# 2.net
KiCad netlist of a schematic drawn in EAGLE
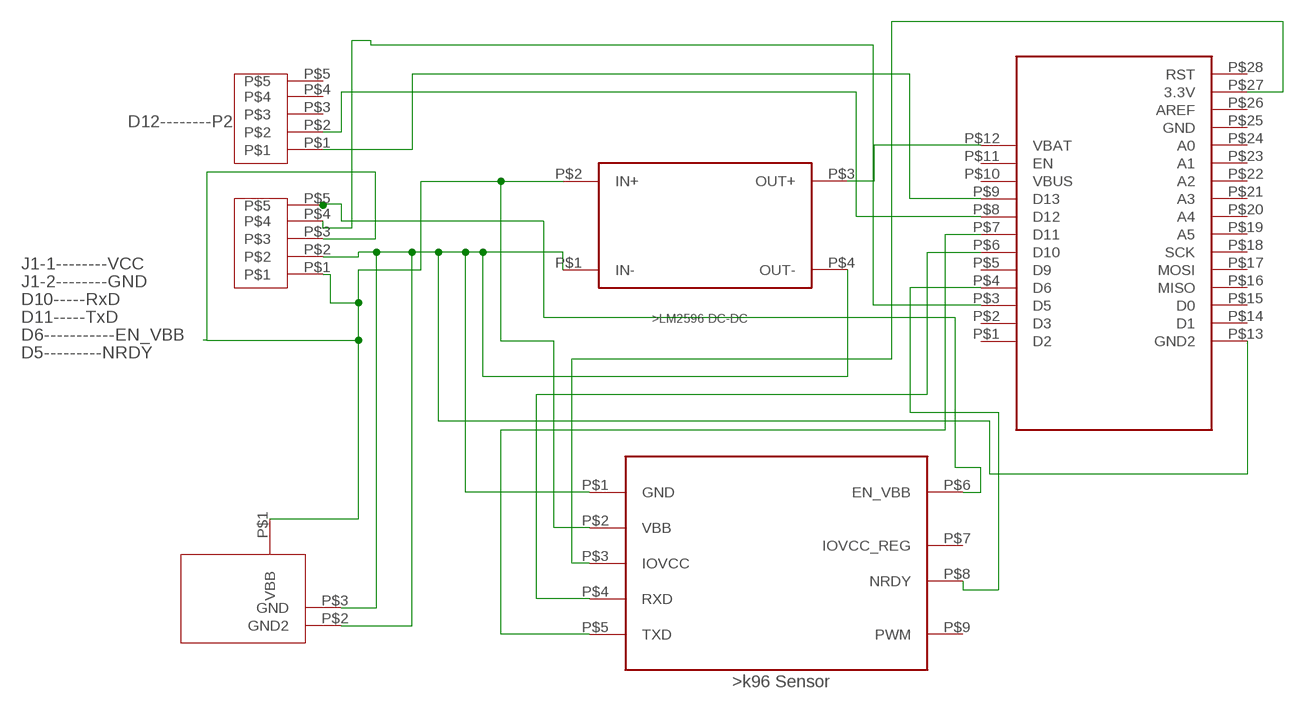
[diagram p0: schematic, sheet 1]

(export (version "E")
  (design (tool "Eeschema 10.0.6"))
  (components
    (comp (ref "DCDC1")
      (value "DCDC")
      (footprint "eagle-import:DCDC")
      (libsource (lib "eagle-import") (part "DCDC"))
    )
    (comp (ref "FEATHER1")
      (value "FEATHER")
      (footprint "eagle-import:FEATHER")
      (libsource (lib "eagle-import") (part "FEATHER"))
    )
    (comp (ref "K96SENSOR1")
      (value "K96SENSOR")
      (footprint "eagle-import:K96SENSOR")
      (libsource (lib "eagle-import") (part "K96SENSOR"))
    )
    (comp (ref "PIN1")
      (value "PIN")
      (footprint "eagle-import:PIN")
      (libsource (lib "eagle-import") (part "PIN"))
    )
    (comp (ref "PIN2")
      (value "PIN")
      (footprint "eagle-import:PIN")
      (libsource (lib "eagle-import") (part "PIN"))
    )
    (comp (ref "U$1")
      (value "POWER")
      (footprint "eagle-import:POWERIN")
      (libsource (lib "eagle-import") (part "POWER"))
    )
  )
  (nets
    (net (code "1") (name "Net-(DCDC1-IN+)") (class "Default")
      (node (ref "DCDC1") (pin "P$2") (pinfunction "IN+_P$2") (pintype "bidirectional"))
      (node (ref "K96SENSOR1") (pin "P$2") (pinfunction "VBB_P$2") (pintype "bidirectional"))
      (node (ref "PIN1") (pin "P$1") (pinfunction "P$1_P$1") (pintype "bidirectional"))
      (node (ref "PIN1") (pin "P$3") (pinfunction "P$3_P$3") (pintype "bidirectional"))
      (node (ref "U$1") (pin "P$1") (pinfunction "VBB_P$1") (pintype "bidirectional"))
    )
    (net (code "2") (name "Net-(DCDC1-IN-)") (class "Default")
      (node (ref "DCDC1") (pin "P$1") (pinfunction "IN-_P$1") (pintype "bidirectional"))
      (node (ref "DCDC1") (pin "P$4") (pinfunction "OUT-_P$4") (pintype "bidirectional"))
      (node (ref "FEATHER1") (pin "P$13") (pinfunction "GND2_P$13") (pintype "bidirectional"))
      (node (ref "K96SENSOR1") (pin "P$1") (pinfunction "GND_P$1") (pintype "bidirectional"))
      (node (ref "PIN1") (pin "P$2") (pinfunction "P$2_P$2") (pintype "bidirectional"))
      (node (ref "U$1") (pin "P$2") (pinfunction "GND2_P$2") (pintype "bidirectional"))
      (node (ref "U$1") (pin "P$3") (pinfunction "GND_P$3") (pintype "bidirectional"))
    )
    (net (code "3") (name "Net-(DCDC1-OUT+)") (class "Default")
      (node (ref "DCDC1") (pin "P$3") (pinfunction "OUT+_P$3") (pintype "bidirectional"))
      (node (ref "FEATHER1") (pin "P$12") (pinfunction "VBAT_P$12") (pintype "bidirectional"))
    )
    (net (code "4") (name "Net-(FEATHER1-3.3V)") (class "Default")
      (node (ref "FEATHER1") (pin "P$27") (pinfunction "3.3V_P$27") (pintype "bidirectional"))
      (node (ref "K96SENSOR1") (pin "P$3") (pinfunction "IOVCC_P$3") (pintype "bidirectional"))
    )
    (net (code "5") (name "Net-(FEATHER1-D5)") (class "Default")
      (node (ref "FEATHER1") (pin "P$3") (pinfunction "D5_P$3") (pintype "bidirectional"))
      (node (ref "PIN1") (pin "P$4") (pinfunction "P$4_P$4") (pintype "bidirectional"))
    )
    (net (code "6") (name "Net-(FEATHER1-D6)") (class "Default")
      (node (ref "FEATHER1") (pin "P$4") (pinfunction "D6_P$4") (pintype "bidirectional"))
      (node (ref "K96SENSOR1") (pin "P$8") (pinfunction "NRDY_P$8") (pintype "bidirectional"))
    )
    (net (code "7") (name "Net-(FEATHER1-D10)") (class "Default")
      (node (ref "FEATHER1") (pin "P$6") (pinfunction "D10_P$6") (pintype "bidirectional"))
      (node (ref "K96SENSOR1") (pin "P$4") (pinfunction "RXD_P$4") (pintype "bidirectional"))
    )
    (net (code "8") (name "Net-(FEATHER1-D11)") (class "Default")
      (node (ref "FEATHER1") (pin "P$7") (pinfunction "D11_P$7") (pintype "bidirectional"))
      (node (ref "K96SENSOR1") (pin "P$5") (pinfunction "TXD_P$5") (pintype "bidirectional"))
    )
    (net (code "9") (name "Net-(FEATHER1-D12)") (class "Default")
      (node (ref "FEATHER1") (pin "P$8") (pinfunction "D12_P$8") (pintype "bidirectional"))
      (node (ref "PIN2") (pin "P$2") (pinfunction "P$2_P$2") (pintype "bidirectional"))
    )
    (net (code "10") (name "Net-(FEATHER1-D13)") (class "Default")
      (node (ref "FEATHER1") (pin "P$9") (pinfunction "D13_P$9") (pintype "bidirectional"))
      (node (ref "PIN2") (pin "P$1") (pinfunction "P$1_P$1") (pintype "bidirectional"))
    )
    (net (code "11") (name "Net-(K96SENSOR1-EN_VBB)") (class "Default")
      (node (ref "K96SENSOR1") (pin "P$6") (pinfunction "EN_VBB_P$6") (pintype "bidirectional"))
      (node (ref "PIN1") (pin "P$5") (pinfunction "P$5_P$5") (pintype "bidirectional"))
    )
    (net (code "12") (name "unconnected-(FEATHER1-A0-PadP$24)") (class "Default")
      (node (ref "FEATHER1") (pin "P$24") (pinfunction "A0_P$24") (pintype "bidirectional"))
    )
    (net (code "13") (name "unconnected-(FEATHER1-A1-PadP$23)") (class "Default")
      (node (ref "FEATHER1") (pin "P$23") (pinfunction "A1_P$23") (pintype "bidirectional"))
    )
    (net (code "14") (name "unconnected-(FEATHER1-A2-PadP$22)") (class "Default")
      (node (ref "FEATHER1") (pin "P$22") (pinfunction "A2_P$22") (pintype "bidirectional"))
    )
    (net (code "15") (name "unconnected-(FEATHER1-A3-PadP$21)") (class "Default")
      (node (ref "FEATHER1") (pin "P$21") (pinfunction "A3_P$21") (pintype "bidirectional"))
    )
    (net (code "16") (name "unconnected-(FEATHER1-A4-PadP$20)") (class "Default")
      (node (ref "FEATHER1") (pin "P$20") (pinfunction "A4_P$20") (pintype "bidirectional"))
    )
    (net (code "17") (name "unconnected-(FEATHER1-A5-PadP$19)") (class "Default")
      (node (ref "FEATHER1") (pin "P$19") (pinfunction "A5_P$19") (pintype "bidirectional"))
    )
    (net (code "18") (name "unconnected-(FEATHER1-AREF-PadP$26)") (class "Default")
      (node (ref "FEATHER1") (pin "P$26") (pinfunction "AREF_P$26") (pintype "bidirectional"))
    )
    (net (code "19") (name "unconnected-(FEATHER1-D0-PadP$15)") (class "Default")
      (node (ref "FEATHER1") (pin "P$15") (pinfunction "D0_P$15") (pintype "bidirectional"))
    )
    (net (code "20") (name "unconnected-(FEATHER1-D1-PadP$14)") (class "Default")
      (node (ref "FEATHER1") (pin "P$14") (pinfunction "D1_P$14") (pintype "bidirectional"))
    )
    (net (code "21") (name "unconnected-(FEATHER1-D2-PadP$1)") (class "Default")
      (node (ref "FEATHER1") (pin "P$1") (pinfunction "D2_P$1") (pintype "bidirectional"))
    )
    (net (code "22") (name "unconnected-(FEATHER1-D3-PadP$2)") (class "Default")
      (node (ref "FEATHER1") (pin "P$2") (pinfunction "D3_P$2") (pintype "bidirectional"))
    )
    (net (code "23") (name "unconnected-(FEATHER1-D9-PadP$5)") (class "Default")
      (node (ref "FEATHER1") (pin "P$5") (pinfunction "D9_P$5") (pintype "bidirectional"))
    )
    (net (code "24") (name "unconnected-(FEATHER1-EN-PadP$11)") (class "Default")
      (node (ref "FEATHER1") (pin "P$11") (pinfunction "EN_P$11") (pintype "bidirectional"))
    )
    (net (code "25") (name "unconnected-(FEATHER1-GND-PadP$25)") (class "Default")
      (node (ref "FEATHER1") (pin "P$25") (pinfunction "GND_P$25") (pintype "bidirectional"))
    )
    (net (code "26") (name "unconnected-(FEATHER1-MISO-PadP$16)") (class "Default")
      (node (ref "FEATHER1") (pin "P$16") (pinfunction "MISO_P$16") (pintype "bidirectional"))
    )
    (net (code "27") (name "unconnected-(FEATHER1-MOSI-PadP$17)") (class "Default")
      (node (ref "FEATHER1") (pin "P$17") (pinfunction "MOSI_P$17") (pintype "bidirectional"))
    )
    (net (code "28") (name "unconnected-(FEATHER1-RST-PadP$28)") (class "Default")
      (node (ref "FEATHER1") (pin "P$28") (pinfunction "RST_P$28") (pintype "bidirectional"))
    )
    (net (code "29") (name "unconnected-(FEATHER1-SCK-PadP$18)") (class "Default")
      (node (ref "FEATHER1") (pin "P$18") (pinfunction "SCK_P$18") (pintype "bidirectional"))
    )
    (net (code "30") (name "unconnected-(FEATHER1-VBUS-PadP$10)") (class "Default")
      (node (ref "FEATHER1") (pin "P$10") (pinfunction "VBUS_P$10") (pintype "bidirectional"))
    )
    (net (code "31") (name "unconnected-(K96SENSOR1-IOVCC_REG-PadP$7)") (class "Default")
      (node (ref "K96SENSOR1") (pin "P$7") (pinfunction "IOVCC_REG_P$7") (pintype "bidirectional"))
    )
    (net (code "32") (name "unconnected-(K96SENSOR1-PWM-PadP$9)") (class "Default")
      (node (ref "K96SENSOR1") (pin "P$9") (pinfunction "PWM_P$9") (pintype "bidirectional"))
    )
    (net (code "33") (name "unconnected-(PIN2-PadP$3)") (class "Default")
      (node (ref "PIN2") (pin "P$3") (pinfunction "P$3_P$3") (pintype "bidirectional"))
    )
    (net (code "34") (name "unconnected-(PIN2-PadP$4)") (class "Default")
      (node (ref "PIN2") (pin "P$4") (pinfunction "P$4_P$4") (pintype "bidirectional"))
    )
    (net (code "35") (name "unconnected-(PIN2-PadP$5)") (class "Default")
      (node (ref "PIN2") (pin "P$5") (pinfunction "P$5_P$5") (pintype "bidirectional"))
    )
  )
)
